# probatio-arduino-shield_-_c_pia.net
KiCad netlist of a schematic drawn in EAGLE
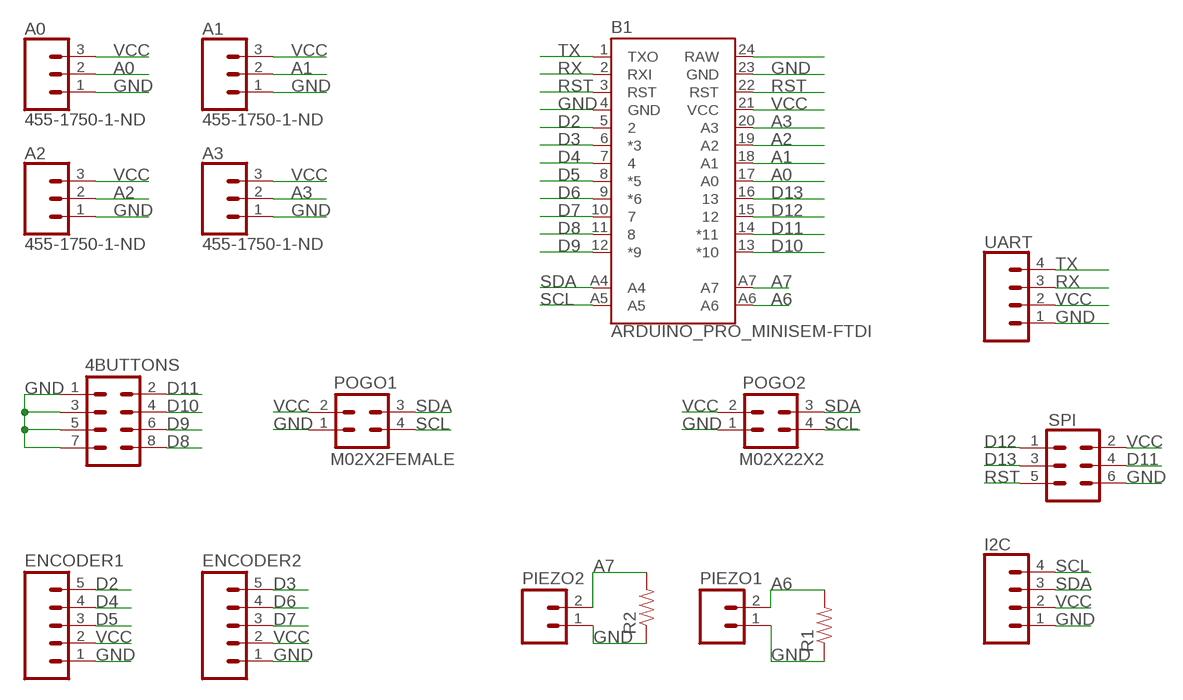
[diagram p0: schematic, sheet 1]

(export (version "E")
  (design (tool "Eeschema 10.0.6"))
  (components
    (comp (ref "4BUTTONS")
      (value "M04X2")
      (footprint "eagle-import:2X4")
      (libsource (lib "eagle-import") (part "M04X2"))
    )
    (comp (ref "A0")
      (value "455-1750-1-ND")
      (footprint "eagle-import:1X03")
      (libsource (lib "eagle-import") (part "CONN_03"))
    )
    (comp (ref "A1")
      (value "455-1750-1-ND")
      (footprint "eagle-import:1X03")
      (libsource (lib "eagle-import") (part "CONN_03"))
    )
    (comp (ref "A2")
      (value "455-1750-1-ND")
      (footprint "eagle-import:1X03")
      (libsource (lib "eagle-import") (part "CONN_03"))
    )
    (comp (ref "A3")
      (value "455-1750-1-ND")
      (footprint "eagle-import:1X03")
      (libsource (lib "eagle-import") (part "CONN_03"))
    )
    (comp (ref "B1")
      (value "ARDUINO_PRO_MINISEM-FTDI")
      (footprint "eagle-import:ARDUINO_PRO_MINI_S_FTDI")
      (libsource (lib "eagle-import") (part "ARDUINO_PRO_MINISEM-FTDI"))
    )
    (comp (ref "ENCODER1")
      (value "M05PTH")
      (footprint "eagle-import:1X05")
      (libsource (lib "eagle-import") (part "M05PTH"))
    )
    (comp (ref "ENCODER2")
      (value "M05PTH")
      (footprint "eagle-import:1X05")
      (libsource (lib "eagle-import") (part "M05PTH"))
    )
    (comp (ref "I2C")
      (value "CONN_04PTH")
      (footprint "eagle-import:1X04")
      (libsource (lib "eagle-import") (part "CONN_04PTH"))
    )
    (comp (ref "PIEZO1")
      (value "M02PTH")
      (footprint "eagle-import:1X02")
      (libsource (lib "eagle-import") (part "M02PTH"))
    )
    (comp (ref "PIEZO2")
      (value "M02PTH")
      (footprint "eagle-import:1X02")
      (libsource (lib "eagle-import") (part "M02PTH"))
    )
    (comp (ref "POGO1")
      (value "M02X2FEMALE")
      (footprint "eagle-import:2X2INV")
      (libsource (lib "eagle-import") (part "M02X2FEMALE"))
    )
    (comp (ref "POGO2")
      (value "M02X22X2")
      (footprint "eagle-import:2X2")
      (libsource (lib "eagle-import") (part "M02X22X2"))
    )
    (comp (ref "R1")
      (value "RESISTORPTH-1/4W")
      (footprint "eagle-import:AXIAL-0.4")
      (libsource (lib "eagle-import") (part "RESISTORPTH-1/4W"))
    )
    (comp (ref "R2")
      (value "RESISTORPTH-1/4W")
      (footprint "eagle-import:AXIAL-0.4")
      (libsource (lib "eagle-import") (part "RESISTORPTH-1/4W"))
    )
    (comp (ref "SPI")
      (value "CONN_03X2FEMALE")
      (footprint "eagle-import:2X3")
      (libsource (lib "eagle-import") (part "CONN_03X2FEMALE"))
    )
    (comp (ref "UART")
      (value "CONN_04PTH")
      (footprint "eagle-import:1X04")
      (libsource (lib "eagle-import") (part "CONN_04PTH"))
    )
  )
  (nets
    (net (code "1") (name "/A0") (class "Default")
      (node (ref "A0") (pin "2") (pinfunction "2_2") (pintype "passive"))
      (node (ref "B1") (pin "17") (pinfunction "A0_17") (pintype "bidirectional"))
    )
    (net (code "2") (name "/A1") (class "Default")
      (node (ref "A1") (pin "2") (pinfunction "2_2") (pintype "passive"))
      (node (ref "B1") (pin "18") (pinfunction "A1_18") (pintype "bidirectional"))
    )
    (net (code "3") (name "/A2") (class "Default")
      (node (ref "A2") (pin "2") (pinfunction "2_2") (pintype "passive"))
      (node (ref "B1") (pin "19") (pinfunction "A2_19") (pintype "bidirectional"))
    )
    (net (code "4") (name "/A3") (class "Default")
      (node (ref "A3") (pin "2") (pinfunction "2_2") (pintype "passive"))
      (node (ref "B1") (pin "20") (pinfunction "A3_20") (pintype "bidirectional"))
    )
    (net (code "5") (name "/A6") (class "Default")
      (node (ref "B1") (pin "A6") (pinfunction "A6_A6") (pintype "bidirectional"))
      (node (ref "PIEZO1") (pin "2") (pinfunction "2_2") (pintype "passive"))
      (node (ref "R1") (pin "P$2") (pinfunction "2_P$2") (pintype "passive"))
    )
    (net (code "6") (name "/A7") (class "Default")
      (node (ref "B1") (pin "A7") (pinfunction "A7_A7") (pintype "bidirectional"))
      (node (ref "PIEZO2") (pin "2") (pinfunction "2_2") (pintype "passive"))
      (node (ref "R2") (pin "P$2") (pinfunction "2_P$2") (pintype "passive"))
    )
    (net (code "7") (name "/D2") (class "Default")
      (node (ref "B1") (pin "5") (pinfunction "2_5") (pintype "bidirectional"))
      (node (ref "ENCODER1") (pin "5") (pinfunction "5_5") (pintype "passive"))
    )
    (net (code "8") (name "/D3") (class "Default")
      (node (ref "B1") (pin "6") (pinfunction "*3_6") (pintype "bidirectional"))
      (node (ref "ENCODER2") (pin "5") (pinfunction "5_5") (pintype "passive"))
    )
    (net (code "9") (name "/D4") (class "Default")
      (node (ref "B1") (pin "7") (pinfunction "4_7") (pintype "bidirectional"))
      (node (ref "ENCODER1") (pin "4") (pinfunction "4_4") (pintype "passive"))
    )
    (net (code "10") (name "/D5") (class "Default")
      (node (ref "B1") (pin "8") (pinfunction "*5_8") (pintype "bidirectional"))
      (node (ref "ENCODER1") (pin "3") (pinfunction "3_3") (pintype "passive"))
    )
    (net (code "11") (name "/D6") (class "Default")
      (node (ref "B1") (pin "9") (pinfunction "*6_9") (pintype "bidirectional"))
      (node (ref "ENCODER2") (pin "4") (pinfunction "4_4") (pintype "passive"))
    )
    (net (code "12") (name "/D7") (class "Default")
      (node (ref "B1") (pin "10") (pinfunction "7_10") (pintype "bidirectional"))
      (node (ref "ENCODER2") (pin "3") (pinfunction "3_3") (pintype "passive"))
    )
    (net (code "13") (name "/D8") (class "Default")
      (node (ref "4BUTTONS") (pin "8") (pinfunction "8_8") (pintype "passive"))
      (node (ref "B1") (pin "11") (pinfunction "8_11") (pintype "bidirectional"))
    )
    (net (code "14") (name "/D9") (class "Default")
      (node (ref "4BUTTONS") (pin "6") (pinfunction "6_6") (pintype "passive"))
      (node (ref "B1") (pin "12") (pinfunction "*9_12") (pintype "bidirectional"))
    )
    (net (code "15") (name "/D10") (class "Default")
      (node (ref "4BUTTONS") (pin "4") (pinfunction "4_4") (pintype "passive"))
      (node (ref "B1") (pin "13") (pinfunction "*10_13") (pintype "bidirectional"))
    )
    (net (code "16") (name "/D11") (class "Default")
      (node (ref "4BUTTONS") (pin "2") (pinfunction "2_2") (pintype "passive"))
      (node (ref "B1") (pin "14") (pinfunction "*11_14") (pintype "bidirectional"))
      (node (ref "SPI") (pin "4") (pinfunction "4_4") (pintype "bidirectional"))
    )
    (net (code "17") (name "/D12") (class "Default")
      (node (ref "B1") (pin "15") (pinfunction "12_15") (pintype "bidirectional"))
      (node (ref "SPI") (pin "1") (pinfunction "1_1") (pintype "bidirectional"))
    )
    (net (code "18") (name "/D13") (class "Default")
      (node (ref "B1") (pin "16") (pinfunction "13_16") (pintype "bidirectional"))
      (node (ref "SPI") (pin "3") (pinfunction "3_3") (pintype "bidirectional"))
    )
    (net (code "19") (name "/GND") (class "Default")
      (node (ref "4BUTTONS") (pin "1") (pinfunction "1_1") (pintype "passive"))
      (node (ref "4BUTTONS") (pin "3") (pinfunction "3_3") (pintype "passive"))
      (node (ref "4BUTTONS") (pin "5") (pinfunction "5_5") (pintype "passive"))
      (node (ref "4BUTTONS") (pin "7") (pinfunction "7_7") (pintype "passive"))
      (node (ref "A0") (pin "1") (pinfunction "1_1") (pintype "passive"))
      (node (ref "A1") (pin "1") (pinfunction "1_1") (pintype "passive"))
      (node (ref "A2") (pin "1") (pinfunction "1_1") (pintype "passive"))
      (node (ref "A3") (pin "1") (pinfunction "1_1") (pintype "passive"))
      (node (ref "B1") (pin "23") (pinfunction "GND_23") (pintype "power_in"))
      (node (ref "B1") (pin "4") (pinfunction "GND_4") (pintype "power_in"))
      (node (ref "ENCODER1") (pin "1") (pinfunction "1_1") (pintype "passive"))
      (node (ref "ENCODER2") (pin "1") (pinfunction "1_1") (pintype "passive"))
      (node (ref "I2C") (pin "1") (pinfunction "1_1") (pintype "passive"))
      (node (ref "PIEZO1") (pin "1") (pinfunction "1_1") (pintype "passive"))
      (node (ref "PIEZO2") (pin "1") (pinfunction "1_1") (pintype "passive"))
      (node (ref "POGO1") (pin "1") (pinfunction "1_1") (pintype "passive"))
      (node (ref "POGO2") (pin "1") (pinfunction "1_1") (pintype "passive"))
      (node (ref "R1") (pin "P$1") (pinfunction "1_P$1") (pintype "passive"))
      (node (ref "R2") (pin "P$1") (pinfunction "1_P$1") (pintype "passive"))
      (node (ref "SPI") (pin "6") (pinfunction "6_6") (pintype "bidirectional"))
      (node (ref "UART") (pin "1") (pinfunction "1_1") (pintype "passive"))
    )
    (net (code "20") (name "/RST") (class "Default")
      (node (ref "B1") (pin "22") (pinfunction "RST_22") (pintype "bidirectional"))
      (node (ref "B1") (pin "3") (pinfunction "RST_3") (pintype "bidirectional"))
      (node (ref "SPI") (pin "5") (pinfunction "5_5") (pintype "bidirectional"))
    )
    (net (code "21") (name "/RX") (class "Default")
      (node (ref "B1") (pin "2") (pinfunction "RXI_2") (pintype "bidirectional"))
      (node (ref "UART") (pin "3") (pinfunction "3_3") (pintype "passive"))
    )
    (net (code "22") (name "/SCL") (class "Default")
      (node (ref "B1") (pin "A5") (pinfunction "A5_A5") (pintype "bidirectional"))
      (node (ref "I2C") (pin "4") (pinfunction "4_4") (pintype "passive"))
      (node (ref "POGO1") (pin "4") (pinfunction "4_4") (pintype "passive"))
      (node (ref "POGO2") (pin "4") (pinfunction "4_4") (pintype "passive"))
    )
    (net (code "23") (name "/SDA") (class "Default")
      (node (ref "B1") (pin "A4") (pinfunction "A4_A4") (pintype "bidirectional"))
      (node (ref "I2C") (pin "3") (pinfunction "3_3") (pintype "passive"))
      (node (ref "POGO1") (pin "3") (pinfunction "3_3") (pintype "passive"))
      (node (ref "POGO2") (pin "3") (pinfunction "3_3") (pintype "passive"))
    )
    (net (code "24") (name "/TX") (class "Default")
      (node (ref "B1") (pin "1") (pinfunction "TXO_1") (pintype "bidirectional"))
      (node (ref "UART") (pin "4") (pinfunction "4_4") (pintype "passive"))
    )
    (net (code "25") (name "/VCC") (class "Default")
      (node (ref "A0") (pin "3") (pinfunction "3_3") (pintype "passive"))
      (node (ref "A1") (pin "3") (pinfunction "3_3") (pintype "passive"))
      (node (ref "A2") (pin "3") (pinfunction "3_3") (pintype "passive"))
      (node (ref "A3") (pin "3") (pinfunction "3_3") (pintype "passive"))
      (node (ref "B1") (pin "21") (pinfunction "VCC_21") (pintype "power_in"))
      (node (ref "ENCODER1") (pin "2") (pinfunction "2_2") (pintype "passive"))
      (node (ref "ENCODER2") (pin "2") (pinfunction "2_2") (pintype "passive"))
      (node (ref "I2C") (pin "2") (pinfunction "2_2") (pintype "passive"))
      (node (ref "POGO1") (pin "2") (pinfunction "2_2") (pintype "passive"))
      (node (ref "POGO2") (pin "2") (pinfunction "2_2") (pintype "passive"))
      (node (ref "SPI") (pin "2") (pinfunction "2_2") (pintype "bidirectional"))
      (node (ref "UART") (pin "2") (pinfunction "2_2") (pintype "passive"))
    )
    (net (code "26") (name "unconnected-(B1-RAW-Pad24)") (class "Default")
      (node (ref "B1") (pin "24") (pinfunction "RAW_24") (pintype "power_in"))
    )
  )
)
